# design.net
KiCad netlist of a schematic drawn in Altium Designer
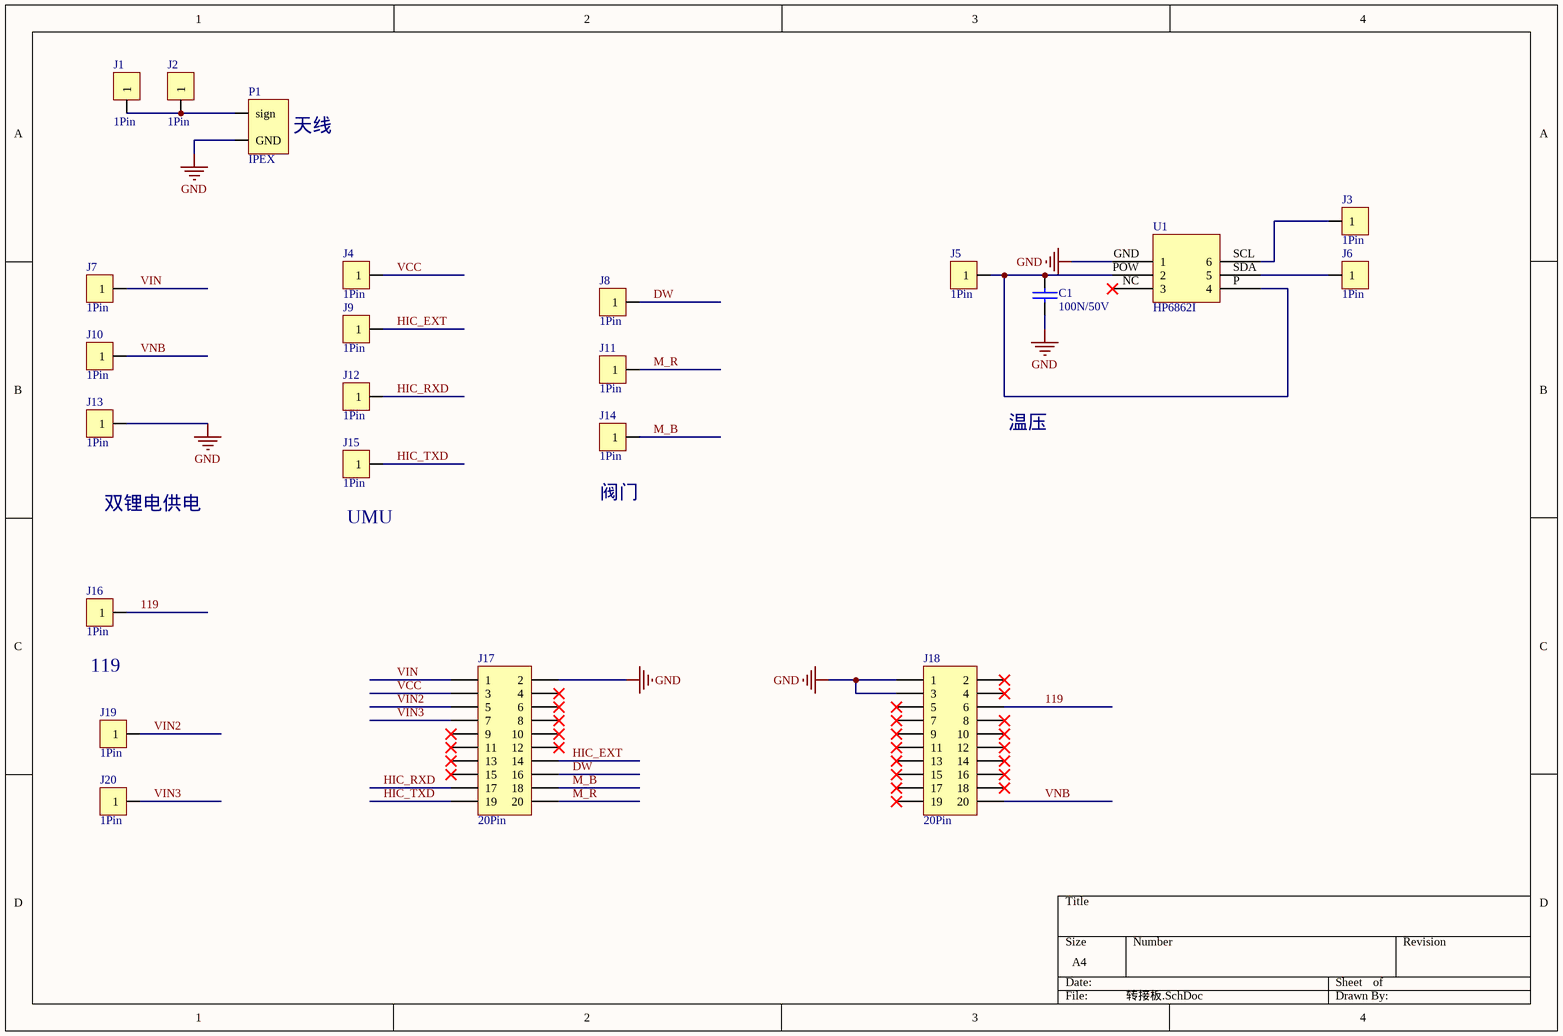
[diagram p0: 转接板.SchDoc]

(export (version "E")
  (design (tool "Eeschema 10.0.6"))
  (components
    (comp (ref "C1")
      (value "100N/50V")
      (footprint "CAP0603")
      (description "100N/50V，±10%，0603")
      (fields (field (name "PART NUMBER") "101020103-0021"))
      (libsource (lib "转接板封装") (part "CC03K7R9B_100N"))
    )
    (comp (ref "J1") (value "1Pin") (footprint "顶针孔1") (libsource (lib "") (part "1Pin_1")))
    (comp (ref "J2") (value "1Pin") (footprint "顶针孔1") (libsource (lib "") (part "1Pin_1")))
    (comp (ref "J3") (value "1Pin") (footprint "顶针孔1") (libsource (lib "") (part "1Pin_2")))
    (comp (ref "J4") (value "1Pin") (footprint "顶针孔1") (libsource (lib "转接板封装") (part "1Pin")))
    (comp (ref "J5") (value "1Pin") (footprint "顶针孔1") (libsource (lib "转接板封装") (part "1Pin")))
    (comp (ref "J6") (value "1Pin") (footprint "顶针孔1") (libsource (lib "") (part "1Pin_2")))
    (comp (ref "J7") (value "1Pin") (footprint "顶针孔1") (libsource (lib "转接板封装") (part "1Pin")))
    (comp (ref "J8") (value "1Pin") (footprint "顶针孔1") (libsource (lib "转接板封装") (part "1Pin")))
    (comp (ref "J9") (value "1Pin") (footprint "顶针孔1") (libsource (lib "转接板封装") (part "1Pin")))
    (comp (ref "J10") (value "1Pin") (footprint "顶针孔1") (libsource (lib "转接板封装") (part "1Pin")))
    (comp (ref "J11") (value "1Pin") (footprint "顶针孔1") (libsource (lib "转接板封装") (part "1Pin")))
    (comp (ref "J12") (value "1Pin") (footprint "顶针孔1") (libsource (lib "转接板封装") (part "1Pin")))
    (comp (ref "J13") (value "1Pin") (footprint "顶针孔1") (libsource (lib "转接板封装") (part "1Pin")))
    (comp (ref "J14") (value "1Pin") (footprint "顶针孔1") (libsource (lib "转接板封装") (part "1Pin")))
    (comp (ref "J15") (value "1Pin") (footprint "顶针孔1") (libsource (lib "转接板封装") (part "1Pin")))
    (comp (ref "J16") (value "1Pin") (footprint "顶针孔1") (libsource (lib "转接板封装") (part "1Pin")))
    (comp (ref "J17")
      (value "20Pin")
      (footprint "DC254_2*10 - duplicate")
      (description "DC2 2.54mm 2x10pin,2.54mm间距，2x10pin，32×8.55×27.5mm,母头,双排,双排牛角座")
      (fields (field (name "PART NUMBER") "1010902-0139"))
      (libsource (lib "转接板封装") (part "20Pin"))
    )
    (comp (ref "J18")
      (value "20Pin")
      (footprint "DC254_2*10 - duplicate")
      (description "DC2 2.54mm 2x10pin,2.54mm间距，2x10pin，32×8.55×27.5mm,母头,双排,双排牛角座")
      (fields (field (name "PART NUMBER") "1010902-0139"))
      (libsource (lib "转接板封装") (part "20Pin"))
    )
    (comp (ref "J19") (value "1Pin") (footprint "顶针孔1") (libsource (lib "转接板封装") (part "1Pin")))
    (comp (ref "J20") (value "1Pin") (footprint "顶针孔1") (libsource (lib "转接板封装") (part "1Pin")))
    (comp (ref "P1") (value "IPEX") (footprint "ANT-IPEX") (libsource (lib "转接板封装") (part "IPEX")))
    (comp (ref "U1") (value "HP6862I") (footprint "HP6862") (libsource (lib "转接板封装") (part "HP6862I")))
  )
  (nets
    (net (code "1") (name "/119") (class "Default")
      (node (ref "J16") (pin "1") (pinfunction "1_1") (pintype "passive"))
      (node (ref "J18") (pin "6") (pinfunction "6_6") (pintype "passive"))
    )
    (net (code "2") (name "/DW") (class "Default")
      (node (ref "J17") (pin "16") (pinfunction "16_16") (pintype "passive"))
      (node (ref "J8") (pin "1") (pinfunction "1_1") (pintype "passive"))
    )
    (net (code "3") (name "/HIC_EXT") (class "Default")
      (node (ref "J17") (pin "14") (pinfunction "14_14") (pintype "passive"))
      (node (ref "J9") (pin "1") (pinfunction "1_1") (pintype "passive"))
    )
    (net (code "4") (name "/HIC_RXD") (class "Default")
      (node (ref "J12") (pin "1") (pinfunction "1_1") (pintype "passive"))
      (node (ref "J17") (pin "17") (pinfunction "17_17") (pintype "passive"))
    )
    (net (code "5") (name "/HIC_TXD") (class "Default")
      (node (ref "J15") (pin "1") (pinfunction "1_1") (pintype "passive"))
      (node (ref "J17") (pin "19") (pinfunction "19_19") (pintype "passive"))
    )
    (net (code "6") (name "/M_B") (class "Default")
      (node (ref "J14") (pin "1") (pinfunction "1_1") (pintype "passive"))
      (node (ref "J17") (pin "18") (pinfunction "18_18") (pintype "passive"))
    )
    (net (code "7") (name "/M_R") (class "Default")
      (node (ref "J11") (pin "1") (pinfunction "1_1") (pintype "passive"))
      (node (ref "J17") (pin "20") (pinfunction "20_20") (pintype "passive"))
    )
    (net (code "8") (name "/VCC") (class "Default")
      (node (ref "J17") (pin "3") (pinfunction "3_3") (pintype "passive"))
      (node (ref "J4") (pin "1") (pinfunction "1_1") (pintype "passive"))
    )
    (net (code "9") (name "/VIN") (class "Default")
      (node (ref "J17") (pin "1") (pinfunction "1_1") (pintype "passive"))
      (node (ref "J7") (pin "1") (pinfunction "1_1") (pintype "passive"))
    )
    (net (code "10") (name "/VIN2") (class "Default")
      (node (ref "J17") (pin "5") (pinfunction "5_5") (pintype "passive"))
      (node (ref "J19") (pin "1") (pinfunction "1_1") (pintype "passive"))
    )
    (net (code "11") (name "/VIN3") (class "Default")
      (node (ref "J17") (pin "7") (pinfunction "7_7") (pintype "passive"))
      (node (ref "J20") (pin "1") (pinfunction "1_1") (pintype "passive"))
    )
    (net (code "12") (name "/VNB") (class "Default")
      (node (ref "J10") (pin "1") (pinfunction "1_1") (pintype "passive"))
      (node (ref "J18") (pin "20") (pinfunction "20_20") (pintype "passive"))
    )
    (net (code "13") (name "GND") (class "Default")
      (node (ref "C1") (pin "2") (pinfunction "2_2") (pintype "passive"))
      (node (ref "J13") (pin "1") (pinfunction "1_1") (pintype "passive"))
      (node (ref "J17") (pin "2") (pinfunction "2_2") (pintype "passive"))
      (node (ref "J18") (pin "1") (pinfunction "1_1") (pintype "passive"))
      (node (ref "J18") (pin "3") (pinfunction "3_3") (pintype "passive"))
      (node (ref "P1") (pin "2") (pinfunction "GND_2") (pintype "passive"))
      (node (ref "U1") (pin "GND") (pinfunction "1_GND") (pintype "passive"))
    )
    (net (code "14") (name "Net-(P1-sign)") (class "Default")
      (node (ref "J1") (pin "1") (pinfunction "1_1") (pintype "passive"))
      (node (ref "J2") (pin "1") (pinfunction "1_1") (pintype "passive"))
      (node (ref "P1") (pin "1") (pinfunction "sign_1") (pintype "passive"))
    )
    (net (code "15") (name "Net-(U1-2)") (class "Default")
      (node (ref "C1") (pin "1") (pinfunction "1_1") (pintype "passive"))
      (node (ref "J5") (pin "1") (pinfunction "1_1") (pintype "passive"))
      (node (ref "U1") (pin "P") (pinfunction "4_P") (pintype "passive"))
      (node (ref "U1") (pin "POW") (pinfunction "2_POW") (pintype "passive"))
    )
    (net (code "16") (name "Net-(U1-5)") (class "Default")
      (node (ref "J6") (pin "1") (pinfunction "1_1") (pintype "passive"))
      (node (ref "U1") (pin "SDA") (pinfunction "5_SDA") (pintype "passive"))
    )
    (net (code "17") (name "Net-(U1-6)") (class "Default")
      (node (ref "J3") (pin "1") (pinfunction "1_1") (pintype "passive"))
      (node (ref "U1") (pin "SCL") (pinfunction "6_SCL") (pintype "passive"))
    )
    (net (code "18") (name "unconnected-(J17-Pad4)") (class "Default")
      (node (ref "J17") (pin "4") (pinfunction "4_4") (pintype "passive+no_connect"))
    )
    (net (code "19") (name "unconnected-(J17-Pad6)") (class "Default")
      (node (ref "J17") (pin "6") (pinfunction "6_6") (pintype "passive+no_connect"))
    )
    (net (code "20") (name "unconnected-(J17-Pad8)") (class "Default")
      (node (ref "J17") (pin "8") (pinfunction "8_8") (pintype "passive+no_connect"))
    )
    (net (code "21") (name "unconnected-(J17-Pad9)") (class "Default")
      (node (ref "J17") (pin "9") (pinfunction "9_9") (pintype "passive+no_connect"))
    )
    (net (code "22") (name "unconnected-(J17-Pad10)") (class "Default")
      (node (ref "J17") (pin "10") (pinfunction "10_10") (pintype "passive+no_connect"))
    )
    (net (code "23") (name "unconnected-(J17-Pad11)") (class "Default")
      (node (ref "J17") (pin "11") (pinfunction "11_11") (pintype "passive+no_connect"))
    )
    (net (code "24") (name "unconnected-(J17-Pad12)") (class "Default")
      (node (ref "J17") (pin "12") (pinfunction "12_12") (pintype "passive+no_connect"))
    )
    (net (code "25") (name "unconnected-(J17-Pad13)") (class "Default")
      (node (ref "J17") (pin "13") (pinfunction "13_13") (pintype "passive+no_connect"))
    )
    (net (code "26") (name "unconnected-(J17-Pad15)") (class "Default")
      (node (ref "J17") (pin "15") (pinfunction "15_15") (pintype "passive+no_connect"))
    )
    (net (code "27") (name "unconnected-(J18-Pad2)") (class "Default")
      (node (ref "J18") (pin "2") (pinfunction "2_2") (pintype "passive+no_connect"))
    )
    (net (code "28") (name "unconnected-(J18-Pad4)") (class "Default")
      (node (ref "J18") (pin "4") (pinfunction "4_4") (pintype "passive+no_connect"))
    )
    (net (code "29") (name "unconnected-(J18-Pad5)") (class "Default")
      (node (ref "J18") (pin "5") (pinfunction "5_5") (pintype "passive+no_connect"))
    )
    (net (code "30") (name "unconnected-(J18-Pad7)") (class "Default")
      (node (ref "J18") (pin "7") (pinfunction "7_7") (pintype "passive+no_connect"))
    )
    (net (code "31") (name "unconnected-(J18-Pad8)") (class "Default")
      (node (ref "J18") (pin "8") (pinfunction "8_8") (pintype "passive+no_connect"))
    )
    (net (code "32") (name "unconnected-(J18-Pad9)") (class "Default")
      (node (ref "J18") (pin "9") (pinfunction "9_9") (pintype "passive+no_connect"))
    )
    (net (code "33") (name "unconnected-(J18-Pad10)") (class "Default")
      (node (ref "J18") (pin "10") (pinfunction "10_10") (pintype "passive+no_connect"))
    )
    (net (code "34") (name "unconnected-(J18-Pad11)") (class "Default")
      (node (ref "J18") (pin "11") (pinfunction "11_11") (pintype "passive+no_connect"))
    )
    (net (code "35") (name "unconnected-(J18-Pad12)") (class "Default")
      (node (ref "J18") (pin "12") (pinfunction "12_12") (pintype "passive+no_connect"))
    )
    (net (code "36") (name "unconnected-(J18-Pad13)") (class "Default")
      (node (ref "J18") (pin "13") (pinfunction "13_13") (pintype "passive+no_connect"))
    )
    (net (code "37") (name "unconnected-(J18-Pad14)") (class "Default")
      (node (ref "J18") (pin "14") (pinfunction "14_14") (pintype "passive+no_connect"))
    )
    (net (code "38") (name "unconnected-(J18-Pad15)") (class "Default")
      (node (ref "J18") (pin "15") (pinfunction "15_15") (pintype "passive+no_connect"))
    )
    (net (code "39") (name "unconnected-(J18-Pad16)") (class "Default")
      (node (ref "J18") (pin "16") (pinfunction "16_16") (pintype "passive+no_connect"))
    )
    (net (code "40") (name "unconnected-(J18-Pad17)") (class "Default")
      (node (ref "J18") (pin "17") (pinfunction "17_17") (pintype "passive+no_connect"))
    )
    (net (code "41") (name "unconnected-(J18-Pad18)") (class "Default")
      (node (ref "J18") (pin "18") (pinfunction "18_18") (pintype "passive+no_connect"))
    )
    (net (code "42") (name "unconnected-(J18-Pad19)") (class "Default")
      (node (ref "J18") (pin "19") (pinfunction "19_19") (pintype "passive+no_connect"))
    )
    (net (code "43") (name "unconnected-(U1-3-PadNC)") (class "Default")
      (node (ref "U1") (pin "NC") (pinfunction "3_NC") (pintype "passive+no_connect"))
    )
  )
)
